# SCH_555-Circuit_2025-11-07.net
KiCad netlist of a schematic drawn in EasyEDA
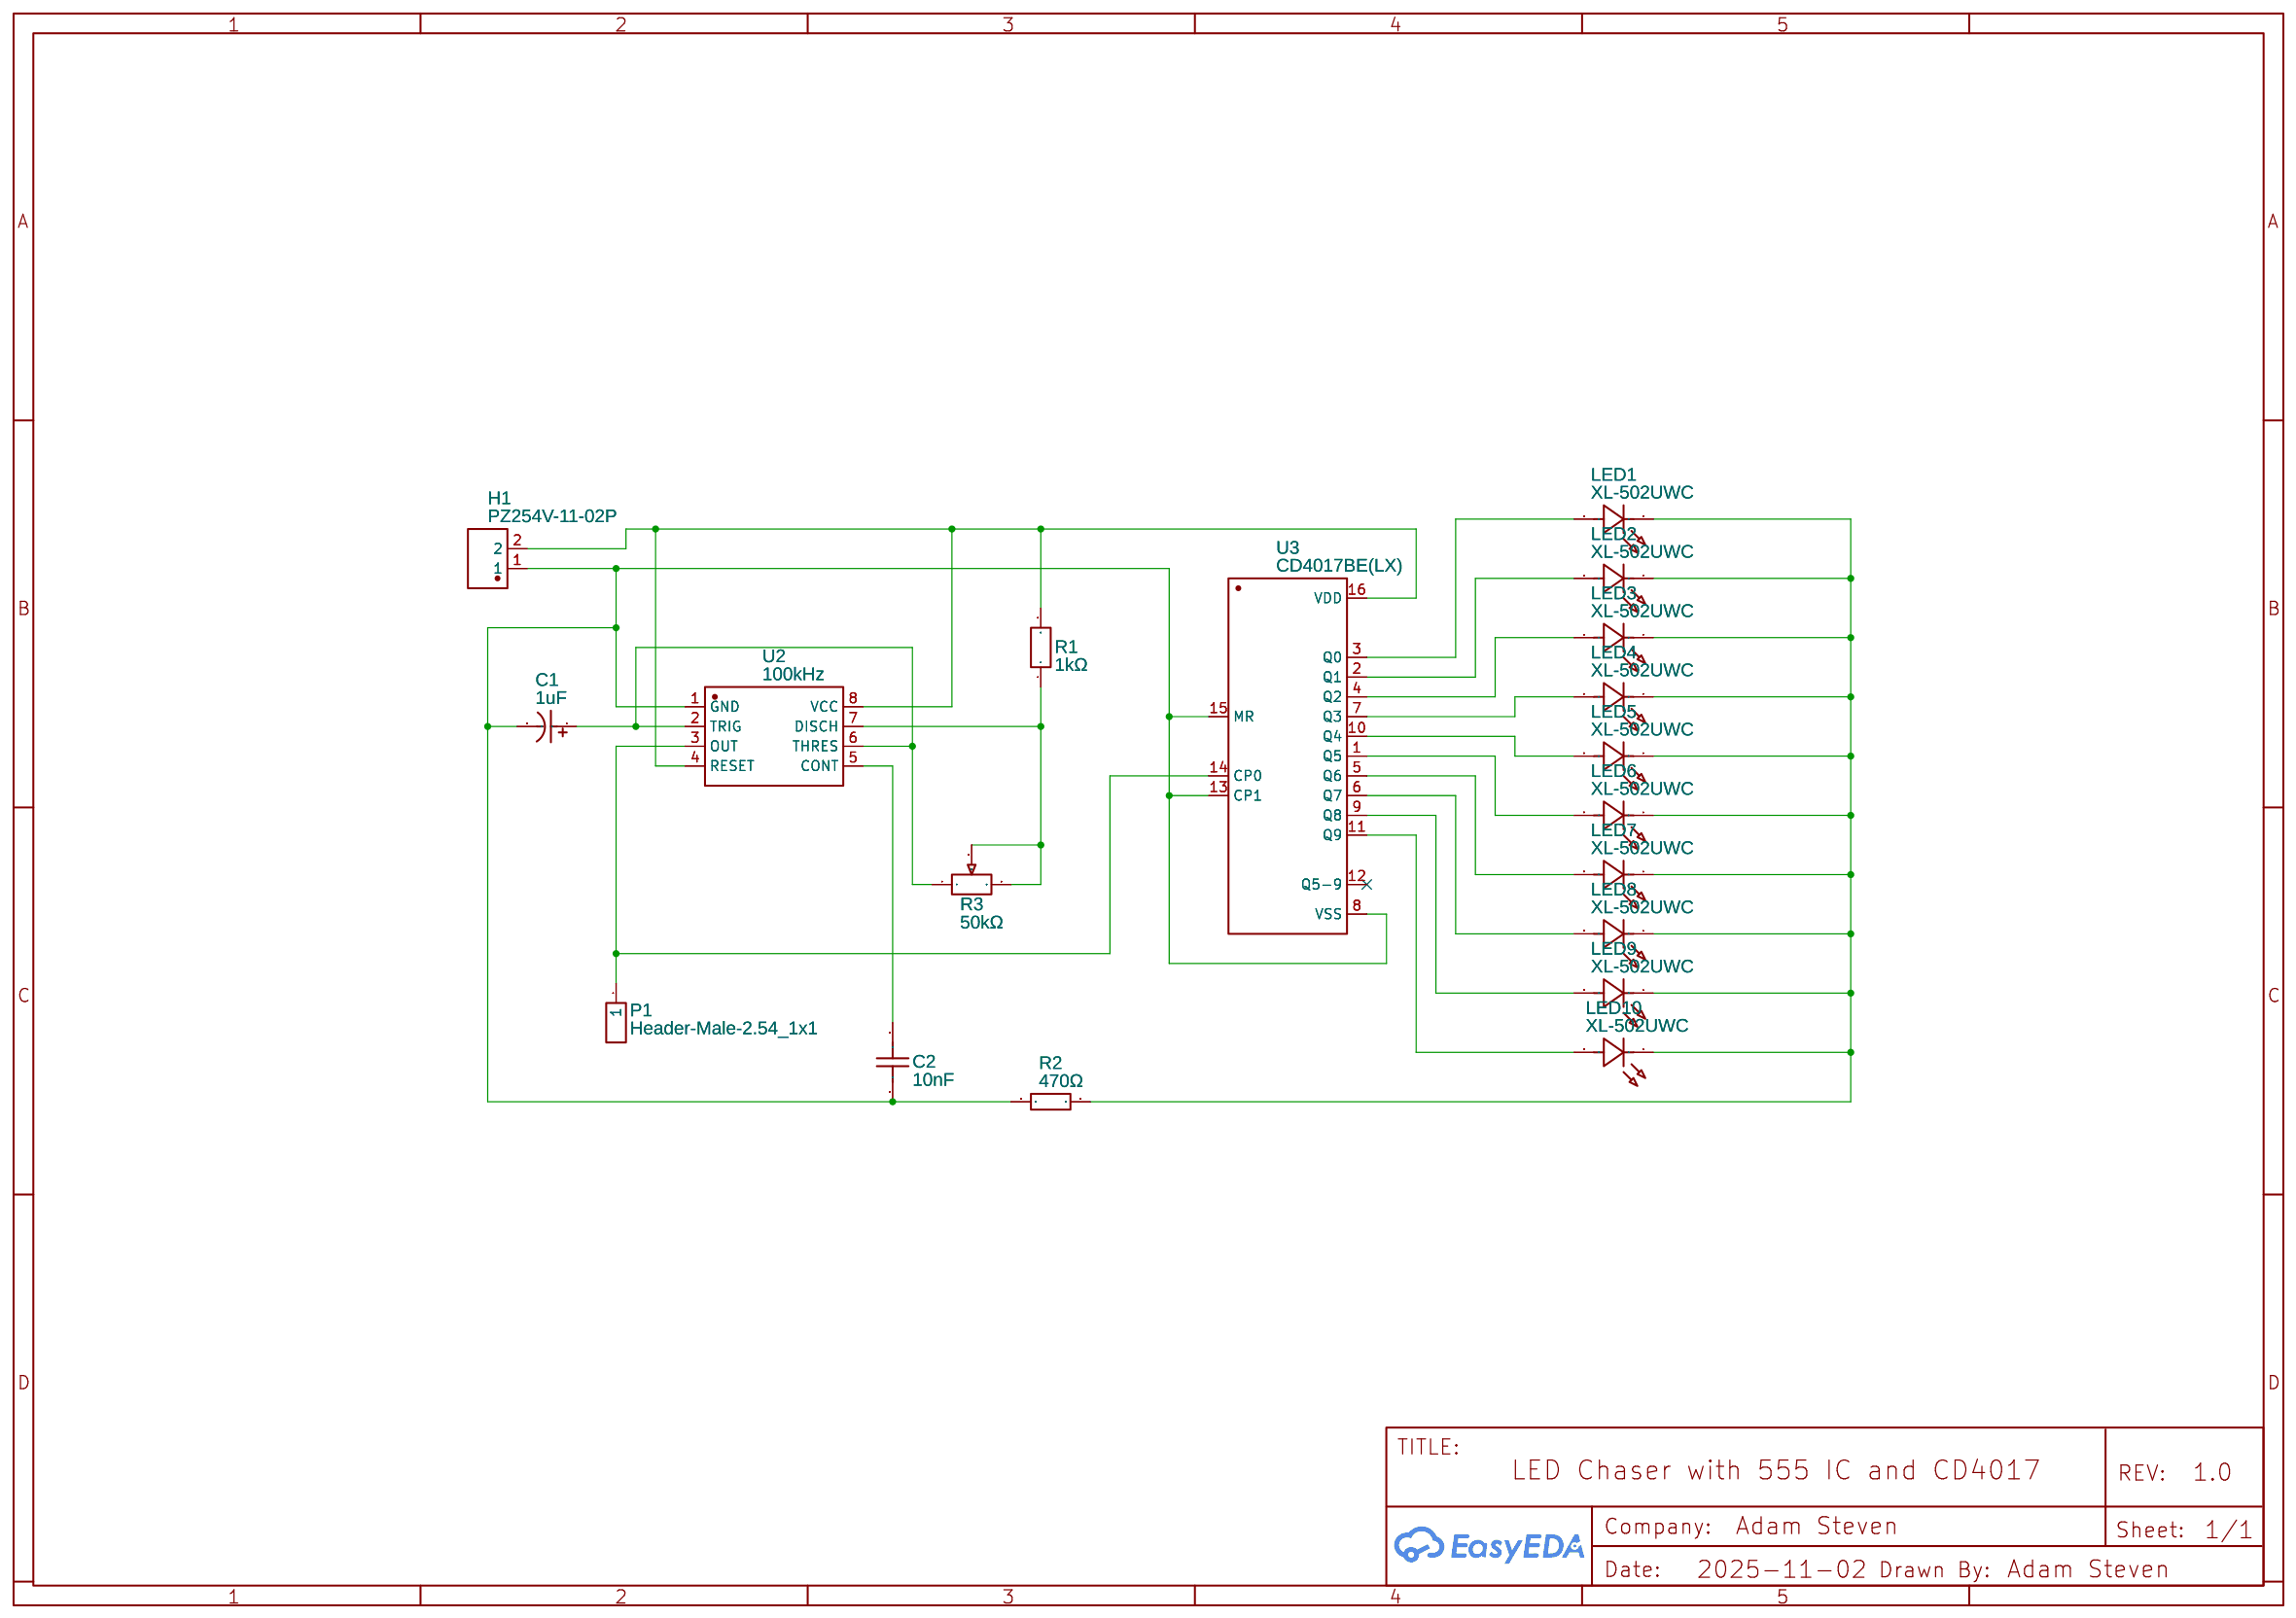
[diagram p0: schematic sheet]

(export (version "E")
  (design (tool "Eeschema 10.0.6"))
  (components
    (comp (ref "C1")
      (value "1uF")
      (fields (field (name "Manufacturer Part") "KF010M050C110A") (field (name "Manufacturer") "CapXon(丰宾)"))
      (libsource (lib "") (part "KF010M050C110A"))
    )
    (comp (ref "C2")
      (value "10nF")
      (fields (field (name "Manufacturer Part") "N09F1B103MN0B0S0N0") (field (name "Manufacturer") "STE(松田)"))
      (libsource (lib "") (part "N09F1B103MN0B0S0N0"))
    )
    (comp (ref "H1")
      (value "PZ254V-11-02P")
      (fields (field (name "Manufacturer") "XFCN(兴飞)"))
      (libsource (lib "") (part "PZ254V-11-02P"))
    )
    (comp (ref "LED1")
      (value "XL-502UWC")
      (fields (field (name "Manufacturer") "XINGLIGHT(成兴光)"))
      (libsource (lib "") (part "XL-502UWC"))
    )
    (comp (ref "LED2")
      (value "XL-502UWC")
      (fields (field (name "Manufacturer") "XINGLIGHT(成兴光)"))
      (libsource (lib "") (part "XL-502UWC"))
    )
    (comp (ref "LED3")
      (value "XL-502UWC")
      (fields (field (name "Manufacturer") "XINGLIGHT(成兴光)"))
      (libsource (lib "") (part "XL-502UWC"))
    )
    (comp (ref "LED4")
      (value "XL-502UWC")
      (fields (field (name "Manufacturer") "XINGLIGHT(成兴光)"))
      (libsource (lib "") (part "XL-502UWC"))
    )
    (comp (ref "LED5")
      (value "XL-502UWC")
      (fields (field (name "Manufacturer") "XINGLIGHT(成兴光)"))
      (libsource (lib "") (part "XL-502UWC"))
    )
    (comp (ref "LED6")
      (value "XL-502UWC")
      (fields (field (name "Manufacturer") "XINGLIGHT(成兴光)"))
      (libsource (lib "") (part "XL-502UWC"))
    )
    (comp (ref "LED7")
      (value "XL-502UWC")
      (fields (field (name "Manufacturer") "XINGLIGHT(成兴光)"))
      (libsource (lib "") (part "XL-502UWC"))
    )
    (comp (ref "LED8")
      (value "XL-502UWC")
      (fields (field (name "Manufacturer") "XINGLIGHT(成兴光)"))
      (libsource (lib "") (part "XL-502UWC"))
    )
    (comp (ref "LED9")
      (value "XL-502UWC")
      (fields (field (name "Manufacturer") "XINGLIGHT(成兴光)"))
      (libsource (lib "") (part "XL-502UWC"))
    )
    (comp (ref "LED10")
      (value "XL-502UWC")
      (fields (field (name "Manufacturer") "XINGLIGHT(成兴光)"))
      (libsource (lib "") (part "XL-502UWC"))
    )
    (comp (ref "P1")
      (value "Header-Male-2.54_1x1")
      (fields (field (name "Manufacturer Part") "2.54-1*1P针") (field (name "Manufacturer") "BOOMELE(博穆精密)"))
      (libsource (lib "") (part "Header-Male-2.54_1x1"))
    )
    (comp (ref "R1")
      (value "1kΩ")
      (fields (field (name "Manufacturer Part") "MF1/4W-1KΩ±1%T52") (field (name "Manufacturer") "华星机电"))
      (libsource (lib "") (part "MF1/4W-1KΩ±1%T52"))
    )
    (comp (ref "R2")
      (value "470Ω")
      (fields
        (field (name "Manufacturer Part") "MFR0W4F4700A50")
        (field (name "Manufacturer") "UNI-ROYAL(厚声)")
      )
      (libsource (lib "") (part "MFR0W4F4700A50"))
    )
    (comp (ref "R3")
      (value "50kΩ")
      (fields (field (name "Manufacturer Part") "3296X-1-503") (field (name "Manufacturer") "BOCHEN(博晨)"))
      (libsource (lib "") (part "3296X-1-503_C118912"))
    )
    (comp (ref "U2")
      (value "100kHz")
      (fields (field (name "Manufacturer Part") "NE555P") (field (name "Manufacturer") "TI(德州仪器)"))
      (libsource (lib "") (part "NE555P"))
    )
    (comp (ref "U3")
      (value "CD4017BE(LX)")
      (fields (field (name "Manufacturer") "LX(灵星芯微)"))
      (libsource (lib "") (part "CD4017BE(LX)"))
    )
  )
  (nets
    (net (code "1") (name "Net-(LED1-A)") (class "Default")
      (node (ref "LED1") (pin "2") (pinfunction "A_2") (pintype "unspecified"))
      (node (ref "U3") (pin "3") (pinfunction "Q0_3") (pintype "unspecified"))
    )
    (net (code "2") (name "Net-(LED1-K)") (class "Default")
      (node (ref "LED1") (pin "1") (pinfunction "K_1") (pintype "unspecified"))
      (node (ref "LED10") (pin "1") (pinfunction "K_1") (pintype "unspecified"))
      (node (ref "LED2") (pin "1") (pinfunction "K_1") (pintype "unspecified"))
      (node (ref "LED3") (pin "1") (pinfunction "K_1") (pintype "unspecified"))
      (node (ref "LED4") (pin "1") (pinfunction "K_1") (pintype "unspecified"))
      (node (ref "LED5") (pin "1") (pinfunction "K_1") (pintype "unspecified"))
      (node (ref "LED6") (pin "1") (pinfunction "K_1") (pintype "unspecified"))
      (node (ref "LED7") (pin "1") (pinfunction "K_1") (pintype "unspecified"))
      (node (ref "LED8") (pin "1") (pinfunction "K_1") (pintype "unspecified"))
      (node (ref "LED9") (pin "1") (pinfunction "K_1") (pintype "unspecified"))
      (node (ref "R2") (pin "2") (pinfunction "2_2") (pintype "input"))
    )
    (net (code "3") (name "Net-(LED2-A)") (class "Default")
      (node (ref "LED2") (pin "2") (pinfunction "A_2") (pintype "unspecified"))
      (node (ref "U3") (pin "2") (pinfunction "Q1_2") (pintype "unspecified"))
    )
    (net (code "4") (name "Net-(LED3-A)") (class "Default")
      (node (ref "LED3") (pin "2") (pinfunction "A_2") (pintype "unspecified"))
      (node (ref "U3") (pin "4") (pinfunction "Q2_4") (pintype "unspecified"))
    )
    (net (code "5") (name "Net-(LED4-A)") (class "Default")
      (node (ref "LED4") (pin "2") (pinfunction "A_2") (pintype "unspecified"))
      (node (ref "U3") (pin "7") (pinfunction "Q3_7") (pintype "unspecified"))
    )
    (net (code "6") (name "Net-(LED5-A)") (class "Default")
      (node (ref "LED5") (pin "2") (pinfunction "A_2") (pintype "unspecified"))
      (node (ref "U3") (pin "10") (pinfunction "Q4_10") (pintype "unspecified"))
    )
    (net (code "7") (name "Net-(LED6-A)") (class "Default")
      (node (ref "LED6") (pin "2") (pinfunction "A_2") (pintype "unspecified"))
      (node (ref "U3") (pin "1") (pinfunction "Q5_1") (pintype "unspecified"))
    )
    (net (code "8") (name "Net-(LED7-A)") (class "Default")
      (node (ref "LED7") (pin "2") (pinfunction "A_2") (pintype "unspecified"))
      (node (ref "U3") (pin "5") (pinfunction "Q6_5") (pintype "unspecified"))
    )
    (net (code "9") (name "Net-(LED8-A)") (class "Default")
      (node (ref "LED8") (pin "2") (pinfunction "A_2") (pintype "unspecified"))
      (node (ref "U3") (pin "6") (pinfunction "Q7_6") (pintype "unspecified"))
    )
    (net (code "10") (name "Net-(LED9-A)") (class "Default")
      (node (ref "LED9") (pin "2") (pinfunction "A_2") (pintype "unspecified"))
      (node (ref "U3") (pin "9") (pinfunction "Q8_9") (pintype "unspecified"))
    )
    (net (code "11") (name "Net-(LED10-A)") (class "Default")
      (node (ref "LED10") (pin "2") (pinfunction "A_2") (pintype "unspecified"))
      (node (ref "U3") (pin "11") (pinfunction "Q9_11") (pintype "unspecified"))
    )
    (net (code "12") (name "Net-(U2-CONT)") (class "Default")
      (node (ref "C2") (pin "2") (pinfunction "2_2") (pintype "unspecified"))
      (node (ref "U2") (pin "5") (pinfunction "CONT_5") (pintype "unspecified"))
    )
    (net (code "13") (name "Net-(U2-DISCH)") (class "Default")
      (node (ref "R1") (pin "1") (pinfunction "1_1") (pintype "unspecified"))
      (node (ref "R3") (pin "2") (pinfunction "2_2") (pintype "input"))
      (node (ref "R3") (pin "3") (pinfunction "3_3") (pintype "input"))
      (node (ref "U2") (pin "7") (pinfunction "DISCH_7") (pintype "unspecified"))
    )
    (net (code "14") (name "Net-(U2-GND)") (class "Default")
      (node (ref "C1") (pin "2") (pinfunction "2_2") (pintype "input"))
      (node (ref "C2") (pin "1") (pinfunction "1_1") (pintype "unspecified"))
      (node (ref "H1") (pin "1") (pinfunction "1_1") (pintype "unspecified"))
      (node (ref "R2") (pin "1") (pinfunction "1_1") (pintype "input"))
      (node (ref "U2") (pin "1") (pinfunction "GND_1") (pintype "unspecified"))
      (node (ref "U3") (pin "13") (pinfunction "CP1_13") (pintype "unspecified"))
      (node (ref "U3") (pin "15") (pinfunction "MR_15") (pintype "unspecified"))
      (node (ref "U3") (pin "8") (pinfunction "VSS_8") (pintype "unspecified"))
    )
    (net (code "15") (name "Net-(U2-OUT)") (class "Default")
      (node (ref "P1") (pin "1") (pinfunction "1_1") (pintype "input"))
      (node (ref "U2") (pin "3") (pinfunction "OUT_3") (pintype "unspecified"))
      (node (ref "U3") (pin "14") (pinfunction "CP0_14") (pintype "unspecified"))
    )
    (net (code "16") (name "Net-(U2-RESET)") (class "Default")
      (node (ref "H1") (pin "2") (pinfunction "2_2") (pintype "unspecified"))
      (node (ref "R1") (pin "2") (pinfunction "2_2") (pintype "unspecified"))
      (node (ref "U2") (pin "4") (pinfunction "RESET_4") (pintype "unspecified"))
      (node (ref "U2") (pin "8") (pinfunction "VCC_8") (pintype "unspecified"))
      (node (ref "U3") (pin "16") (pinfunction "VDD_16") (pintype "unspecified"))
    )
    (net (code "17") (name "Net-(U2-THRES)") (class "Default")
      (node (ref "C1") (pin "1") (pinfunction "1_1") (pintype "input"))
      (node (ref "R3") (pin "1") (pinfunction "1_1") (pintype "input"))
      (node (ref "U2") (pin "2") (pinfunction "TRIG_2") (pintype "unspecified"))
      (node (ref "U2") (pin "6") (pinfunction "THRES_6") (pintype "unspecified"))
    )
    (net (code "18") (name "unconnected-(U3-Q5-9-Pad12)") (class "Default")
      (node (ref "U3") (pin "12") (pinfunction "Q5-9_12") (pintype "unspecified+no_connect"))
    )
  )
)
